# CAMAC_v2.net
KiCad netlist of a schematic drawn in Altium Designer
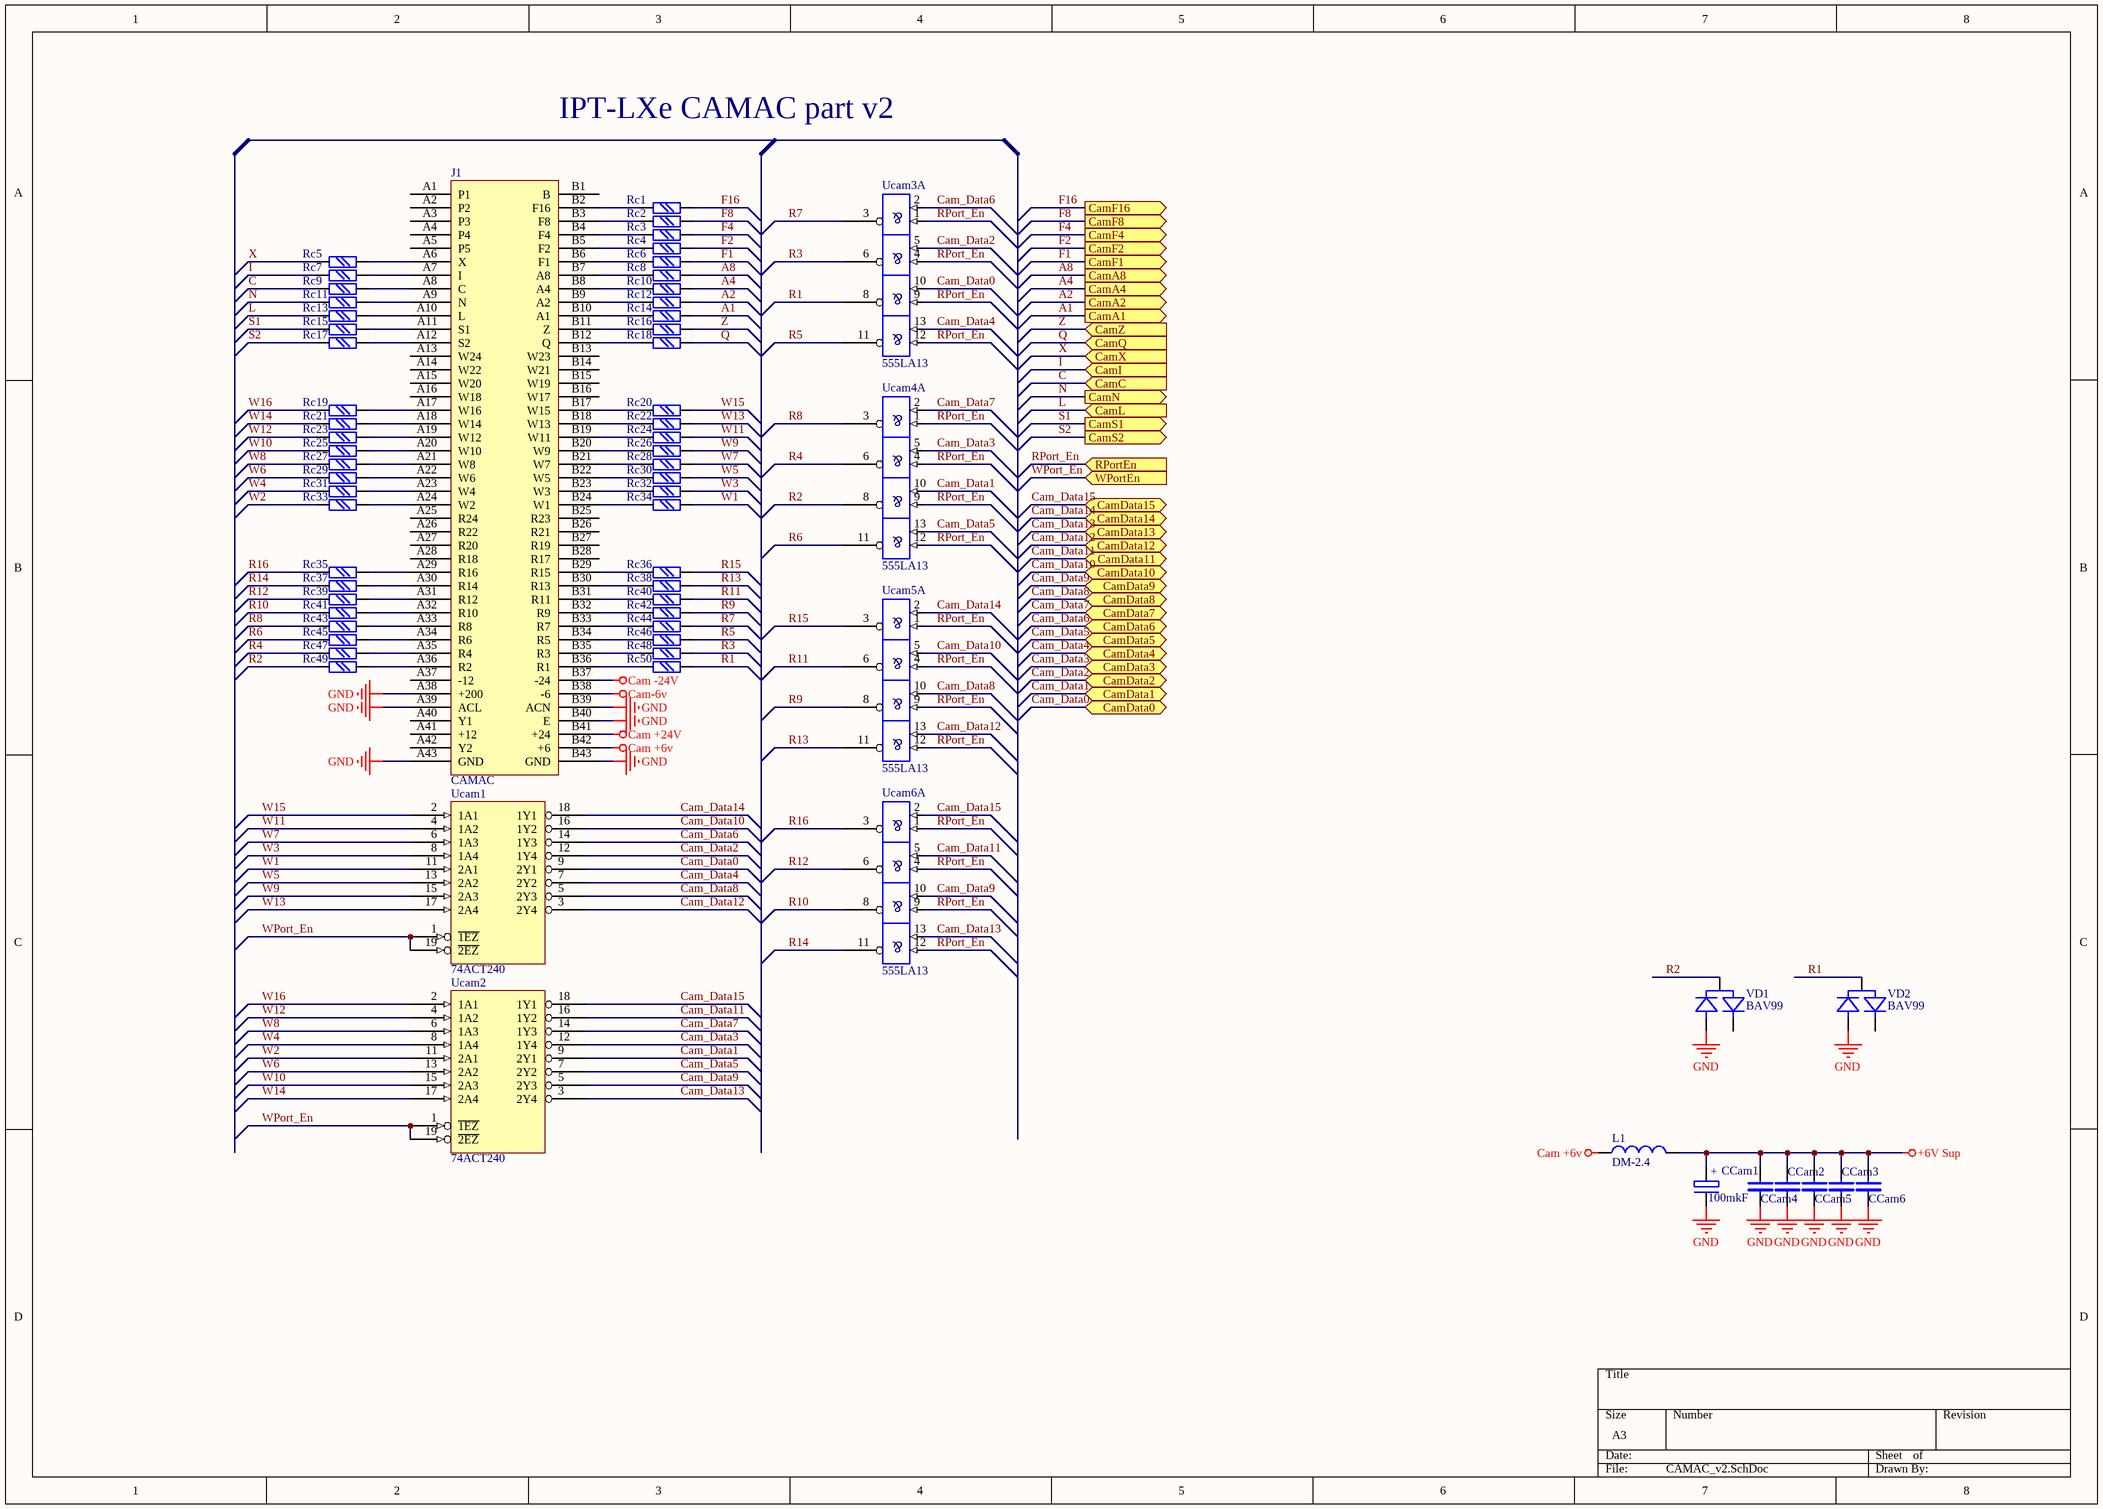
[diagram p0: CAMAC_v2.SchDoc]

(export (version "E")
  (design (tool "Eeschema 10.0.6"))
  (components
    (comp (ref "CCam1") (value "100mkF") (footprint "CEL-SMD300") (libsource (lib "vDevice") (part "C POL")))
    (comp (ref "CCam2") (value "0.1uF") (footprint "chip0805") (libsource (lib "vDevice") (part "C")))
    (comp (ref "CCam3") (value "0.1uF") (footprint "chip0805") (libsource (lib "vDevice") (part "C")))
    (comp (ref "CCam4") (value "0.1uF") (footprint "chip0805") (libsource (lib "vDevice") (part "C")))
    (comp (ref "CCam5") (value "0.1uF") (footprint "chip0805") (libsource (lib "vDevice") (part "C")))
    (comp (ref "CCam6") (value "0.1uF") (footprint "chip0805") (libsource (lib "vDevice") (part "C")))
    (comp (ref "J1") (value "CAMAC") (footprint "CAMAC - duplicate") (libsource (lib "*") (part "CAMACF")))
    (comp (ref "L1") (value "DM-2.4") (footprint "DM-2.4") (libsource (lib "*") (part "INDUCTOR")))
    (comp (ref "Rc1") (value "R") (footprint "chip0805") (libsource (lib "vDevice") (part "R")))
    (comp (ref "Rc2") (value "R") (footprint "chip0805") (libsource (lib "vDevice") (part "R")))
    (comp (ref "Rc3") (value "R") (footprint "chip0805") (libsource (lib "vDevice") (part "R")))
    (comp (ref "Rc4") (value "R") (footprint "chip0805") (libsource (lib "vDevice") (part "R")))
    (comp (ref "Rc5") (value "R") (footprint "chip0805") (libsource (lib "vDevice") (part "R")))
    (comp (ref "Rc6") (value "R") (footprint "chip0805") (libsource (lib "vDevice") (part "R")))
    (comp (ref "Rc7") (value "R") (footprint "chip0805") (libsource (lib "vDevice") (part "R")))
    (comp (ref "Rc8") (value "R") (footprint "chip0805") (libsource (lib "vDevice") (part "R")))
    (comp (ref "Rc9") (value "R") (footprint "chip0805") (libsource (lib "vDevice") (part "R")))
    (comp (ref "Rc10") (value "R") (footprint "chip0805") (libsource (lib "vDevice") (part "R")))
    (comp (ref "Rc11") (value "R") (footprint "chip0805") (libsource (lib "vDevice") (part "R")))
    (comp (ref "Rc12") (value "R") (footprint "chip0805") (libsource (lib "vDevice") (part "R")))
    (comp (ref "Rc13") (value "R") (footprint "chip0805") (libsource (lib "vDevice") (part "R")))
    (comp (ref "Rc14") (value "R") (footprint "chip0805") (libsource (lib "vDevice") (part "R")))
    (comp (ref "Rc15") (value "R") (footprint "chip0805") (libsource (lib "vDevice") (part "R")))
    (comp (ref "Rc16") (value "R") (footprint "chip0805") (libsource (lib "vDevice") (part "R")))
    (comp (ref "Rc17") (value "R") (footprint "chip0805") (libsource (lib "vDevice") (part "R")))
    (comp (ref "Rc18") (value "R") (footprint "chip0805") (libsource (lib "vDevice") (part "R")))
    (comp (ref "Rc19") (value "R") (footprint "chip0805") (libsource (lib "vDevice") (part "R")))
    (comp (ref "Rc20") (value "R") (footprint "chip0805") (libsource (lib "vDevice") (part "R")))
    (comp (ref "Rc21") (value "R") (footprint "chip0805") (libsource (lib "vDevice") (part "R")))
    (comp (ref "Rc22") (value "R") (footprint "chip0805") (libsource (lib "vDevice") (part "R")))
    (comp (ref "Rc23") (value "R") (footprint "chip0805") (libsource (lib "vDevice") (part "R")))
    (comp (ref "Rc24") (value "R") (footprint "chip0805") (libsource (lib "vDevice") (part "R")))
    (comp (ref "Rc25") (value "R") (footprint "chip0805") (libsource (lib "vDevice") (part "R")))
    (comp (ref "Rc26") (value "R") (footprint "chip0805") (libsource (lib "vDevice") (part "R")))
    (comp (ref "Rc27") (value "R") (footprint "chip0805") (libsource (lib "vDevice") (part "R")))
    (comp (ref "Rc28") (value "R") (footprint "chip0805") (libsource (lib "vDevice") (part "R")))
    (comp (ref "Rc29") (value "R") (footprint "chip0805") (libsource (lib "vDevice") (part "R")))
    (comp (ref "Rc30") (value "R") (footprint "chip0805") (libsource (lib "vDevice") (part "R")))
    (comp (ref "Rc31") (value "R") (footprint "chip0805") (libsource (lib "vDevice") (part "R")))
    (comp (ref "Rc32") (value "R") (footprint "chip0805") (libsource (lib "vDevice") (part "R")))
    (comp (ref "Rc33") (value "R") (footprint "chip0805") (libsource (lib "vDevice") (part "R")))
    (comp (ref "Rc34") (value "R") (footprint "chip0805") (libsource (lib "vDevice") (part "R")))
    (comp (ref "Rc35") (value "R") (footprint "chip0805") (libsource (lib "vDevice") (part "R")))
    (comp (ref "Rc36") (value "R") (footprint "chip0805") (libsource (lib "vDevice") (part "R")))
    (comp (ref "Rc37") (value "R") (footprint "chip0805") (libsource (lib "vDevice") (part "R")))
    (comp (ref "Rc38") (value "R") (footprint "chip0805") (libsource (lib "vDevice") (part "R")))
    (comp (ref "Rc39") (value "R") (footprint "chip0805") (libsource (lib "vDevice") (part "R")))
    (comp (ref "Rc40") (value "R") (footprint "chip0805") (libsource (lib "vDevice") (part "R")))
    (comp (ref "Rc41") (value "R") (footprint "chip0805") (libsource (lib "vDevice") (part "R")))
    (comp (ref "Rc42") (value "R") (footprint "chip0805") (libsource (lib "vDevice") (part "R")))
    (comp (ref "Rc43") (value "R") (footprint "chip0805") (libsource (lib "vDevice") (part "R")))
    (comp (ref "Rc44") (value "R") (footprint "chip0805") (libsource (lib "vDevice") (part "R")))
    (comp (ref "Rc45") (value "R") (footprint "chip0805") (libsource (lib "vDevice") (part "R")))
    (comp (ref "Rc46") (value "R") (footprint "chip0805") (libsource (lib "vDevice") (part "R")))
    (comp (ref "Rc47") (value "R") (footprint "chip0805") (libsource (lib "vDevice") (part "R")))
    (comp (ref "Rc48") (value "R") (footprint "chip0805") (libsource (lib "vDevice") (part "R")))
    (comp (ref "Rc49") (value "R") (footprint "chip0805") (libsource (lib "vDevice") (part "R")))
    (comp (ref "Rc50") (value "R") (footprint "chip0805") (libsource (lib "vDevice") (part "R")))
    (comp (ref "Ucam1") (value "74ACT240") (footprint "20SOIC300") (libsource (lib "*") (part "155AP3")))
    (comp (ref "Ucam2") (value "74ACT240") (footprint "20SOIC300") (libsource (lib "*") (part "155AP3")))
    (comp (ref "Ucam3") (value "555LA13") (footprint "14DIP300") (libsource (lib "vTTL") (part "555LA13")))
    (comp (ref "Ucam4") (value "555LA13") (footprint "14DIP300") (libsource (lib "vTTL") (part "555LA13")))
    (comp (ref "Ucam5") (value "555LA13") (footprint "14DIP300") (libsource (lib "vTTL") (part "555LA13")))
    (comp (ref "Ucam6") (value "555LA13") (footprint "14DIP300") (libsource (lib "vTTL") (part "555LA13")))
    (comp (ref "VD1")
      (value "BAV99")
      (footprint "SOT23")
      (description "Double diode")
      (libsource (lib "*") (part "BAV99"))
    )
    (comp (ref "VD2")
      (value "BAV99")
      (footprint "SOT23")
      (description "Double diode")
      (libsource (lib "*") (part "BAV99"))
    )
  )
  (nets
    (net (code "1") (name "+6V Sup") (class "Default")
      (node (ref "CCam1") (pin "+") (pinfunction "+_+") (pintype "passive"))
      (node (ref "CCam2") (pin "1") (pinfunction "1_1") (pintype "passive"))
      (node (ref "CCam3") (pin "1") (pinfunction "1_1") (pintype "passive"))
      (node (ref "CCam4") (pin "1") (pinfunction "1_1") (pintype "passive"))
      (node (ref "CCam5") (pin "1") (pinfunction "1_1") (pintype "passive"))
      (node (ref "CCam6") (pin "1") (pinfunction "1_1") (pintype "passive"))
      (node (ref "L1") (pin "2") (pinfunction "2_2") (pintype "passive"))
    )
    (net (code "2") (name "/A1") (class "Default")
      (node (ref "Rc14") (pin "2") (pinfunction "2_2") (pintype "passive"))
    )
    (net (code "3") (name "/A2") (class "Default")
      (node (ref "Rc12") (pin "2") (pinfunction "2_2") (pintype "passive"))
    )
    (net (code "4") (name "/A4") (class "Default")
      (node (ref "Rc10") (pin "2") (pinfunction "2_2") (pintype "passive"))
    )
    (net (code "5") (name "/A8") (class "Default")
      (node (ref "Rc8") (pin "2") (pinfunction "2_2") (pintype "passive"))
    )
    (net (code "6") (name "/C") (class "Default")
      (node (ref "Rc9") (pin "1") (pinfunction "1_1") (pintype "passive"))
    )
    (net (code "7") (name "/Cam_Data0") (class "Default")
      (node (ref "Ucam1") (pin "9") (pinfunction "2Y1_9") (pintype "tri_state"))
      (node (ref "Ucam3") (pin "10") (pinfunction "I1_10") (pintype "input"))
    )
    (net (code "8") (name "/Cam_Data1") (class "Default")
      (node (ref "Ucam2") (pin "9") (pinfunction "2Y1_9") (pintype "tri_state"))
      (node (ref "Ucam4") (pin "10") (pinfunction "I1_10") (pintype "input"))
    )
    (net (code "9") (name "/Cam_Data2") (class "Default")
      (node (ref "Ucam1") (pin "12") (pinfunction "1Y4_12") (pintype "tri_state"))
      (node (ref "Ucam3") (pin "5") (pinfunction "I1_5") (pintype "input"))
    )
    (net (code "10") (name "/Cam_Data3") (class "Default")
      (node (ref "Ucam2") (pin "12") (pinfunction "1Y4_12") (pintype "tri_state"))
      (node (ref "Ucam4") (pin "5") (pinfunction "I1_5") (pintype "input"))
    )
    (net (code "11") (name "/Cam_Data4") (class "Default")
      (node (ref "Ucam1") (pin "7") (pinfunction "2Y2_7") (pintype "tri_state"))
      (node (ref "Ucam3") (pin "13") (pinfunction "I1_13") (pintype "input"))
    )
    (net (code "12") (name "/Cam_Data5") (class "Default")
      (node (ref "Ucam2") (pin "7") (pinfunction "2Y2_7") (pintype "tri_state"))
      (node (ref "Ucam4") (pin "13") (pinfunction "I1_13") (pintype "input"))
    )
    (net (code "13") (name "/Cam_Data6") (class "Default")
      (node (ref "Ucam1") (pin "14") (pinfunction "1Y3_14") (pintype "tri_state"))
      (node (ref "Ucam3") (pin "2") (pinfunction "I1_2") (pintype "input"))
    )
    (net (code "14") (name "/Cam_Data7") (class "Default")
      (node (ref "Ucam2") (pin "14") (pinfunction "1Y3_14") (pintype "tri_state"))
      (node (ref "Ucam4") (pin "2") (pinfunction "I1_2") (pintype "input"))
    )
    (net (code "15") (name "/Cam_Data8") (class "Default")
      (node (ref "Ucam1") (pin "5") (pinfunction "2Y3_5") (pintype "tri_state"))
      (node (ref "Ucam5") (pin "10") (pinfunction "I1_10") (pintype "input"))
    )
    (net (code "16") (name "/Cam_Data9") (class "Default")
      (node (ref "Ucam2") (pin "5") (pinfunction "2Y3_5") (pintype "tri_state"))
      (node (ref "Ucam6") (pin "10") (pinfunction "I1_10") (pintype "input"))
    )
    (net (code "17") (name "/Cam_Data10") (class "Default")
      (node (ref "Ucam1") (pin "16") (pinfunction "1Y2_16") (pintype "tri_state"))
      (node (ref "Ucam5") (pin "5") (pinfunction "I1_5") (pintype "input"))
    )
    (net (code "18") (name "/Cam_Data11") (class "Default")
      (node (ref "Ucam2") (pin "16") (pinfunction "1Y2_16") (pintype "tri_state"))
      (node (ref "Ucam6") (pin "5") (pinfunction "I1_5") (pintype "input"))
    )
    (net (code "19") (name "/Cam_Data12") (class "Default")
      (node (ref "Ucam1") (pin "3") (pinfunction "2Y4_3") (pintype "tri_state"))
      (node (ref "Ucam5") (pin "13") (pinfunction "I1_13") (pintype "input"))
    )
    (net (code "20") (name "/Cam_Data13") (class "Default")
      (node (ref "Ucam2") (pin "3") (pinfunction "2Y4_3") (pintype "tri_state"))
      (node (ref "Ucam6") (pin "13") (pinfunction "I1_13") (pintype "input"))
    )
    (net (code "21") (name "/Cam_Data14") (class "Default")
      (node (ref "Ucam1") (pin "18") (pinfunction "1Y1_18") (pintype "tri_state"))
      (node (ref "Ucam5") (pin "2") (pinfunction "I1_2") (pintype "input"))
    )
    (net (code "22") (name "/Cam_Data15") (class "Default")
      (node (ref "Ucam2") (pin "18") (pinfunction "1Y1_18") (pintype "tri_state"))
      (node (ref "Ucam6") (pin "2") (pinfunction "I1_2") (pintype "input"))
    )
    (net (code "23") (name "/F1") (class "Default")
      (node (ref "Rc6") (pin "2") (pinfunction "2_2") (pintype "passive"))
    )
    (net (code "24") (name "/F2") (class "Default")
      (node (ref "Rc4") (pin "2") (pinfunction "2_2") (pintype "passive"))
    )
    (net (code "25") (name "/F4") (class "Default")
      (node (ref "Rc3") (pin "2") (pinfunction "2_2") (pintype "passive"))
    )
    (net (code "26") (name "/F8") (class "Default")
      (node (ref "Rc2") (pin "2") (pinfunction "2_2") (pintype "passive"))
    )
    (net (code "27") (name "/F16") (class "Default")
      (node (ref "Rc1") (pin "2") (pinfunction "2_2") (pintype "passive"))
    )
    (net (code "28") (name "/I") (class "Default")
      (node (ref "Rc7") (pin "1") (pinfunction "1_1") (pintype "passive"))
    )
    (net (code "29") (name "/L") (class "Default")
      (node (ref "Rc13") (pin "1") (pinfunction "1_1") (pintype "passive"))
    )
    (net (code "30") (name "/N") (class "Default")
      (node (ref "Rc11") (pin "1") (pinfunction "1_1") (pintype "passive"))
    )
    (net (code "31") (name "/Q") (class "Default")
      (node (ref "Rc18") (pin "2") (pinfunction "2_2") (pintype "passive"))
    )
    (net (code "32") (name "/R1") (class "Default")
      (node (ref "Rc50") (pin "1") (pinfunction "1_1") (pintype "passive"))
      (node (ref "Ucam3") (pin "8") (pinfunction "~{O}_8") (pintype "open_collector"))
      (node (ref "VD2") (pin "3") (pinfunction "3_3") (pintype "passive"))
    )
    (net (code "33") (name "/R2") (class "Default")
      (node (ref "Rc49") (pin "1") (pinfunction "1_1") (pintype "passive"))
      (node (ref "Ucam4") (pin "8") (pinfunction "~{O}_8") (pintype "open_collector"))
      (node (ref "VD1") (pin "3") (pinfunction "3_3") (pintype "passive"))
    )
    (net (code "34") (name "/R3") (class "Default")
      (node (ref "Rc48") (pin "2") (pinfunction "2_2") (pintype "passive"))
      (node (ref "Ucam3") (pin "6") (pinfunction "~{O}_6") (pintype "open_collector"))
    )
    (net (code "35") (name "/R4") (class "Default")
      (node (ref "Rc47") (pin "1") (pinfunction "1_1") (pintype "passive"))
      (node (ref "Ucam4") (pin "6") (pinfunction "~{O}_6") (pintype "open_collector"))
    )
    (net (code "36") (name "/R5") (class "Default")
      (node (ref "Rc46") (pin "2") (pinfunction "2_2") (pintype "passive"))
      (node (ref "Ucam3") (pin "11") (pinfunction "~{O}_11") (pintype "open_collector"))
    )
    (net (code "37") (name "/R6") (class "Default")
      (node (ref "Rc45") (pin "1") (pinfunction "1_1") (pintype "passive"))
      (node (ref "Ucam4") (pin "11") (pinfunction "~{O}_11") (pintype "open_collector"))
    )
    (net (code "38") (name "/R7") (class "Default")
      (node (ref "Rc44") (pin "2") (pinfunction "2_2") (pintype "passive"))
      (node (ref "Ucam3") (pin "3") (pinfunction "~{O}_3") (pintype "open_collector"))
    )
    (net (code "39") (name "/R8") (class "Default")
      (node (ref "Rc43") (pin "1") (pinfunction "1_1") (pintype "passive"))
      (node (ref "Ucam4") (pin "3") (pinfunction "~{O}_3") (pintype "open_collector"))
    )
    (net (code "40") (name "/R9") (class "Default")
      (node (ref "Rc42") (pin "2") (pinfunction "2_2") (pintype "passive"))
      (node (ref "Ucam5") (pin "8") (pinfunction "~{O}_8") (pintype "open_collector"))
    )
    (net (code "41") (name "/R10") (class "Default")
      (node (ref "Rc41") (pin "1") (pinfunction "1_1") (pintype "passive"))
      (node (ref "Ucam6") (pin "8") (pinfunction "~{O}_8") (pintype "open_collector"))
    )
    (net (code "42") (name "/R11") (class "Default")
      (node (ref "Rc40") (pin "2") (pinfunction "2_2") (pintype "passive"))
      (node (ref "Ucam5") (pin "6") (pinfunction "~{O}_6") (pintype "open_collector"))
    )
    (net (code "43") (name "/R12") (class "Default")
      (node (ref "Rc39") (pin "1") (pinfunction "1_1") (pintype "passive"))
      (node (ref "Ucam6") (pin "6") (pinfunction "~{O}_6") (pintype "open_collector"))
    )
    (net (code "44") (name "/R13") (class "Default")
      (node (ref "Rc38") (pin "2") (pinfunction "2_2") (pintype "passive"))
      (node (ref "Ucam5") (pin "11") (pinfunction "~{O}_11") (pintype "open_collector"))
    )
    (net (code "45") (name "/R14") (class "Default")
      (node (ref "Rc37") (pin "1") (pinfunction "1_1") (pintype "passive"))
      (node (ref "Ucam6") (pin "11") (pinfunction "~{O}_11") (pintype "open_collector"))
    )
    (net (code "46") (name "/R15") (class "Default")
      (node (ref "Rc36") (pin "2") (pinfunction "2_2") (pintype "passive"))
      (node (ref "Ucam5") (pin "3") (pinfunction "~{O}_3") (pintype "open_collector"))
    )
    (net (code "47") (name "/R16") (class "Default")
      (node (ref "Rc35") (pin "1") (pinfunction "1_1") (pintype "passive"))
      (node (ref "Ucam6") (pin "3") (pinfunction "~{O}_3") (pintype "open_collector"))
    )
    (net (code "48") (name "/RPort_En") (class "Default")
      (node (ref "Ucam3") (pin "1") (pinfunction "I0_1") (pintype "input"))
      (node (ref "Ucam3") (pin "12") (pinfunction "I0_12") (pintype "input"))
      (node (ref "Ucam3") (pin "4") (pinfunction "I0_4") (pintype "input"))
      (node (ref "Ucam3") (pin "9") (pinfunction "I0_9") (pintype "input"))
      (node (ref "Ucam4") (pin "1") (pinfunction "I0_1") (pintype "input"))
      (node (ref "Ucam4") (pin "12") (pinfunction "I0_12") (pintype "input"))
      (node (ref "Ucam4") (pin "4") (pinfunction "I0_4") (pintype "input"))
      (node (ref "Ucam4") (pin "9") (pinfunction "I0_9") (pintype "input"))
      (node (ref "Ucam5") (pin "1") (pinfunction "I0_1") (pintype "input"))
      (node (ref "Ucam5") (pin "12") (pinfunction "I0_12") (pintype "input"))
      (node (ref "Ucam5") (pin "4") (pinfunction "I0_4") (pintype "input"))
      (node (ref "Ucam5") (pin "9") (pinfunction "I0_9") (pintype "input"))
      (node (ref "Ucam6") (pin "1") (pinfunction "I0_1") (pintype "input"))
      (node (ref "Ucam6") (pin "12") (pinfunction "I0_12") (pintype "input"))
      (node (ref "Ucam6") (pin "4") (pinfunction "I0_4") (pintype "input"))
      (node (ref "Ucam6") (pin "9") (pinfunction "I0_9") (pintype "input"))
    )
    (net (code "49") (name "/S1") (class "Default")
      (node (ref "Rc15") (pin "1") (pinfunction "1_1") (pintype "passive"))
    )
    (net (code "50") (name "/S2") (class "Default")
      (node (ref "Rc17") (pin "1") (pinfunction "1_1") (pintype "passive"))
    )
    (net (code "51") (name "/W1") (class "Default")
      (node (ref "Rc34") (pin "2") (pinfunction "2_2") (pintype "passive"))
      (node (ref "Ucam1") (pin "11") (pinfunction "2A1_11") (pintype "input"))
    )
    (net (code "52") (name "/W2") (class "Default")
      (node (ref "Rc33") (pin "1") (pinfunction "1_1") (pintype "passive"))
      (node (ref "Ucam2") (pin "11") (pinfunction "2A1_11") (pintype "input"))
    )
    (net (code "53") (name "/W3") (class "Default")
      (node (ref "Rc32") (pin "2") (pinfunction "2_2") (pintype "passive"))
      (node (ref "Ucam1") (pin "8") (pinfunction "1A4_8") (pintype "input"))
    )
    (net (code "54") (name "/W4") (class "Default")
      (node (ref "Rc31") (pin "1") (pinfunction "1_1") (pintype "passive"))
      (node (ref "Ucam2") (pin "8") (pinfunction "1A4_8") (pintype "input"))
    )
    (net (code "55") (name "/W5") (class "Default")
      (node (ref "Rc30") (pin "2") (pinfunction "2_2") (pintype "passive"))
      (node (ref "Ucam1") (pin "13") (pinfunction "2A2_13") (pintype "input"))
    )
    (net (code "56") (name "/W6") (class "Default")
      (node (ref "Rc29") (pin "1") (pinfunction "1_1") (pintype "passive"))
      (node (ref "Ucam2") (pin "13") (pinfunction "2A2_13") (pintype "input"))
    )
    (net (code "57") (name "/W7") (class "Default")
      (node (ref "Rc28") (pin "2") (pinfunction "2_2") (pintype "passive"))
      (node (ref "Ucam1") (pin "6") (pinfunction "1A3_6") (pintype "input"))
    )
    (net (code "58") (name "/W8") (class "Default")
      (node (ref "Rc27") (pin "1") (pinfunction "1_1") (pintype "passive"))
      (node (ref "Ucam2") (pin "6") (pinfunction "1A3_6") (pintype "input"))
    )
    (net (code "59") (name "/W9") (class "Default")
      (node (ref "Rc26") (pin "2") (pinfunction "2_2") (pintype "passive"))
      (node (ref "Ucam1") (pin "15") (pinfunction "2A3_15") (pintype "input"))
    )
    (net (code "60") (name "/W10") (class "Default")
      (node (ref "Rc25") (pin "1") (pinfunction "1_1") (pintype "passive"))
      (node (ref "Ucam2") (pin "15") (pinfunction "2A3_15") (pintype "input"))
    )
    (net (code "61") (name "/W11") (class "Default")
      (node (ref "Rc24") (pin "2") (pinfunction "2_2") (pintype "passive"))
      (node (ref "Ucam1") (pin "4") (pinfunction "1A2_4") (pintype "input"))
    )
    (net (code "62") (name "/W12") (class "Default")
      (node (ref "Rc23") (pin "1") (pinfunction "1_1") (pintype "passive"))
      (node (ref "Ucam2") (pin "4") (pinfunction "1A2_4") (pintype "input"))
    )
    (net (code "63") (name "/W13") (class "Default")
      (node (ref "Rc22") (pin "2") (pinfunction "2_2") (pintype "passive"))
      (node (ref "Ucam1") (pin "17") (pinfunction "2A4_17") (pintype "input"))
    )
    (net (code "64") (name "/W14") (class "Default")
      (node (ref "Rc21") (pin "1") (pinfunction "1_1") (pintype "passive"))
      (node (ref "Ucam2") (pin "17") (pinfunction "2A4_17") (pintype "input"))
    )
    (net (code "65") (name "/W15") (class "Default")
      (node (ref "Rc20") (pin "2") (pinfunction "2_2") (pintype "passive"))
      (node (ref "Ucam1") (pin "2") (pinfunction "1A1_2") (pintype "input"))
    )
    (net (code "66") (name "/W16") (class "Default")
      (node (ref "Rc19") (pin "1") (pinfunction "1_1") (pintype "passive"))
      (node (ref "Ucam2") (pin "2") (pinfunction "1A1_2") (pintype "input"))
    )
    (net (code "67") (name "/WPort_En") (class "Default")
      (node (ref "Ucam1") (pin "1") (pinfunction "~{1EZ}_1") (pintype "input"))
      (node (ref "Ucam1") (pin "19") (pinfunction "~{2EZ}_19") (pintype "input"))
      (node (ref "Ucam2") (pin "1") (pinfunction "~{1EZ}_1") (pintype "input"))
      (node (ref "Ucam2") (pin "19") (pinfunction "~{2EZ}_19") (pintype "input"))
    )
    (net (code "68") (name "/X") (class "Default")
      (node (ref "Rc5") (pin "1") (pinfunction "1_1") (pintype "passive"))
    )
    (net (code "69") (name "/Z") (class "Default")
      (node (ref "Rc16") (pin "2") (pinfunction "2_2") (pintype "passive"))
    )
    (net (code "70") (name "Cam +6v") (class "Default")
      (node (ref "J1") (pin "B42") (pinfunction "+6_B42") (pintype "passive"))
      (node (ref "L1") (pin "1") (pinfunction "1_1") (pintype "passive"))
    )
    (net (code "71") (name "Cam +24V") (class "Default")
      (node (ref "J1") (pin "B41") (pinfunction "+24_B41") (pintype "passive"))
    )
    (net (code "72") (name "Cam -24V") (class "Default")
      (node (ref "J1") (pin "B37") (pinfunction "-24_B37") (pintype "passive"))
    )
    (net (code "73") (name "Cam-6v") (class "Default")
      (node (ref "J1") (pin "B38") (pinfunction "-6_B38") (pintype "passive"))
    )
    (net (code "74") (name "GND") (class "Default")
      (node (ref "CCam1") (pin "-") (pinfunction "-_-") (pintype "passive"))
      (node (ref "CCam2") (pin "2") (pinfunction "2_2") (pintype "passive"))
      (node (ref "CCam3") (pin "2") (pinfunction "2_2") (pintype "passive"))
      (node (ref "CCam4") (pin "2") (pinfunction "2_2") (pintype "passive"))
      (node (ref "CCam5") (pin "2") (pinfunction "2_2") (pintype "passive"))
      (node (ref "CCam6") (pin "2") (pinfunction "2_2") (pintype "passive"))
      (node (ref "J1") (pin "A38") (pinfunction "+200_A38") (pintype "passive"))
      (node (ref "J1") (pin "A39") (pinfunction "ACL_A39") (pintype "passive"))
      (node (ref "J1") (pin "A43") (pinfunction "GND_A43") (pintype "passive"))
      (node (ref "J1") (pin "B39") (pinfunction "ACN_B39") (pintype "passive"))
      (node (ref "J1") (pin "B40") (pinfunction "E_B40") (pintype "passive"))
      (node (ref "J1") (pin "B43") (pinfunction "GND_B43") (pintype "passive"))
      (node (ref "Ucam1") (pin "10") (pinfunction "GND_10") (pintype "power_in"))
      (node (ref "Ucam2") (pin "10") (pinfunction "GND_10") (pintype "power_in"))
      (node (ref "VD1") (pin "1") (pinfunction "1_1") (pintype "passive"))
      (node (ref "VD2") (pin "1") (pinfunction "1_1") (pintype "passive"))
    )
    (net (code "75") (name "Net-(J1-A1)") (class "Default")
      (node (ref "J1") (pin "B10") (pinfunction "A1_B10") (pintype "passive"))
      (node (ref "Rc14") (pin "1") (pinfunction "1_1") (pintype "passive"))
    )
    (net (code "76") (name "Net-(J1-A2)") (class "Default")
      (node (ref "J1") (pin "B9") (pinfunction "A2_B9") (pintype "passive"))
      (node (ref "Rc12") (pin "1") (pinfunction "1_1") (pintype "passive"))
    )
    (net (code "77") (name "Net-(J1-A4)") (class "Default")
      (node (ref "J1") (pin "B8") (pinfunction "A4_B8") (pintype "passive"))
      (node (ref "Rc10") (pin "1") (pinfunction "1_1") (pintype "passive"))
    )
    (net (code "78") (name "Net-(J1-A8)") (class "Default")
      (node (ref "J1") (pin "B7") (pinfunction "A8_B7") (pintype "passive"))
      (node (ref "Rc8") (pin "1") (pinfunction "1_1") (pintype "passive"))
    )
    (net (code "79") (name "Net-(J1-C)") (class "Default")
      (node (ref "J1") (pin "A8") (pinfunction "C_A8") (pintype "passive"))
      (node (ref "Rc9") (pin "2") (pinfunction "2_2") (pintype "passive"))
    )
    (net (code "80") (name "Net-(J1-F1)") (class "Default")
      (node (ref "J1") (pin "B6") (pinfunction "F1_B6") (pintype "passive"))
      (node (ref "Rc6") (pin "1") (pinfunction "1_1") (pintype "passive"))
    )
    (net (code "81") (name "Net-(J1-F2)") (class "Default")
      (node (ref "J1") (pin "B5") (pinfunction "F2_B5") (pintype "passive"))
      (node (ref "Rc4") (pin "1") (pinfunction "1_1") (pintype "passive"))
    )
    (net (code "82") (name "Net-(J1-F4)") (class "Default")
      (node (ref "J1") (pin "B4") (pinfunction "F4_B4") (pintype "passive"))
      (node (ref "Rc3") (pin "1") (pinfunction "1_1") (pintype "passive"))
    )
    (net (code "83") (name "Net-(J1-F8)") (class "Default")
      (node (ref "J1") (pin "B3") (pinfunction "F8_B3") (pintype "passive"))
      (node (ref "Rc2") (pin "1") (pinfunction "1_1") (pintype "passive"))
    )
    (net (code "84") (name "Net-(J1-F16)") (class "Default")
      (node (ref "J1") (pin "B2") (pinfunction "F16_B2") (pintype "passive"))
      (node (ref "Rc1") (pin "1") (pinfunction "1_1") (pintype "passive"))
    )
    (net (code "85") (name "Net-(J1-I)") (class "Default")
      (node (ref "J1") (pin "A7") (pinfunction "I_A7") (pintype "passive"))
      (node (ref "Rc7") (pin "2") (pinfunction "2_2") (pintype "passive"))
    )
    (net (code "86") (name "Net-(J1-L)") (class "Default")
      (node (ref "J1") (pin "A10") (pinfunction "L_A10") (pintype "passive"))
      (node (ref "Rc13") (pin "2") (pinfunction "2_2") (pintype "passive"))
    )
    (net (code "87") (name "Net-(J1-N)") (class "Default")
      (node (ref "J1") (pin "A9") (pinfunction "N_A9") (pintype "passive"))
      (node (ref "Rc11") (pin "2") (pinfunction "2_2") (pintype "passive"))
    )
    (net (code "88") (name "Net-(J1-Q)") (class "Default")
      (node (ref "J1") (pin "B12") (pinfunction "Q_B12") (pintype "passive"))
      (node (ref "Rc18") (pin "1") (pinfunction "1_1") (pintype "passive"))
    )
    (net (code "89") (name "Net-(J1-R1)") (class "Default")
      (node (ref "J1") (pin "B36") (pinfunction "R1_B36") (pintype "passive"))
      (node (ref "Rc50") (pin "2") (pinfunction "2_2") (pintype "passive"))
    )
    (net (code "90") (name "Net-(J1-R2)") (class "Default")
      (node (ref "J1") (pin "A36") (pinfunction "R2_A36") (pintype "passive"))
      (node (ref "Rc49") (pin "2") (pinfunction "2_2") (pintype "passive"))
    )
    (net (code "91") (name "Net-(J1-R3)") (class "Default")
      (node (ref "J1") (pin "B35") (pinfunction "R3_B35") (pintype "passive"))
      (node (ref "Rc48") (pin "1") (pinfunction "1_1") (pintype "passive"))
    )
    (net (code "92") (name "Net-(J1-R4)") (class "Default")
      (node (ref "J1") (pin "A35") (pinfunction "R4_A35") (pintype "passive"))
      (node (ref "Rc47") (pin "2") (pinfunction "2_2") (pintype "passive"))
    )
    (net (code "93") (name "Net-(J1-R5)") (class "Default")
      (node (ref "J1") (pin "B34") (pinfunction "R5_B34") (pintype "passive"))
      (node (ref "Rc46") (pin "1") (pinfunction "1_1") (pintype "passive"))
    )
    (net (code "94") (name "Net-(J1-R6)") (class "Default")
      (node (ref "J1") (pin "A34") (pinfunction "R6_A34") (pintype "passive"))
      (node (ref "Rc45") (pin "2") (pinfunction "2_2") (pintype "passive"))
    )
    (net (code "95") (name "Net-(J1-R7)") (class "Default")
      (node (ref "J1") (pin "B33") (pinfunction "R7_B33") (pintype "passive"))
      (node (ref "Rc44") (pin "1") (pinfunction "1_1") (pintype "passive"))
    )
    (net (code "96") (name "Net-(J1-R8)") (class "Default")
      (node (ref "J1") (pin "A33") (pinfunction "R8_A33") (pintype "passive"))
      (node (ref "Rc43") (pin "2") (pinfunction "2_2") (pintype "passive"))
    )
    (net (code "97") (name "Net-(J1-R9)") (class "Default")
      (node (ref "J1") (pin "B32") (pinfunction "R9_B32") (pintype "passive"))
      (node (ref "Rc42") (pin "1") (pinfunction "1_1") (pintype "passive"))
    )
    (net (code "98") (name "Net-(J1-R10)") (class "Default")
      (node (ref "J1") (pin "A32") (pinfunction "R10_A32") (pintype "passive"))
      (node (ref "Rc41") (pin "2") (pinfunction "2_2") (pintype "passive"))
    )
    (net (code "99") (name "Net-(J1-R11)") (class "Default")
      (node (ref "J1") (pin "B31") (pinfunction "R11_B31") (pintype "passive"))
      (node (ref "Rc40") (pin "1") (pinfunction "1_1") (pintype "passive"))
    )
    (net (code "100") (name "Net-(J1-R12)") (class "Default")
      (node (ref "J1") (pin "A31") (pinfunction "R12_A31") (pintype "passive"))
      (node (ref "Rc39") (pin "2") (pinfunction "2_2") (pintype "passive"))
    )
    (net (code "101") (name "Net-(J1-R13)") (class "Default")
      (node (ref "J1") (pin "B30") (pinfunction "R13_B30") (pintype "passive"))
      (node (ref "Rc38") (pin "1") (pinfunction "1_1") (pintype "passive"))
    )
    (net (code "102") (name "Net-(J1-R14)") (class "Default")
      (node (ref "J1") (pin "A30") (pinfunction "R14_A30") (pintype "passive"))
      (node (ref "Rc37") (pin "2") (pinfunction "2_2") (pintype "passive"))
    )
    (net (code "103") (name "Net-(J1-R15)") (class "Default")
      (node (ref "J1") (pin "B29") (pinfunction "R15_B29") (pintype "passive"))
      (node (ref "Rc36") (pin "1") (pinfunction "1_1") (pintype "passive"))
    )
    (net (code "104") (name "Net-(J1-R16)") (class "Default")
      (node (ref "J1") (pin "A29") (pinfunction "R16_A29") (pintype "passive"))
      (node (ref "Rc35") (pin "2") (pinfunction "2_2") (pintype "passive"))
    )
    (net (code "105") (name "Net-(J1-S1)") (class "Default")
      (node (ref "J1") (pin "A11") (pinfunction "S1_A11") (pintype "passive"))
      (node (ref "Rc15") (pin "2") (pinfunction "2_2") (pintype "passive"))
    )
    (net (code "106") (name "Net-(J1-S2)") (class "Default")
      (node (ref "J1") (pin "A12") (pinfunction "S2_A12") (pintype "passive"))
      (node (ref "Rc17") (pin "2") (pinfunction "2_2") (pintype "passive"))
    )
    (net (code "107") (name "Net-(J1-W1)") (class "Default")
      (node (ref "J1") (pin "B24") (pinfunction "W1_B24") (pintype "passive"))
      (node (ref "Rc34") (pin "1") (pinfunction "1_1") (pintype "passive"))
    )
    (net (code "108") (name "Net-(J1-W2)") (class "Default")
      (node (ref "J1") (pin "A24") (pinfunction "W2_A24") (pintype "passive"))
      (node (ref "Rc33") (pin "2") (pinfunction "2_2") (pintype "passive"))
    )
    (net (code "109") (name "Net-(J1-W3)") (class "Default")
      (node (ref "J1") (pin "B23") (pinfunction "W3_B23") (pintype "passive"))
      (node (ref "Rc32") (pin "1") (pinfunction "1_1") (pintype "passive"))
    )
    (net (code "110") (name "Net-(J1-W4)") (class "Default")
      (node (ref "J1") (pin "A23") (pinfunction "W4_A23") (pintype "passive"))
      (node (ref "Rc31") (pin "2") (pinfunction "2_2") (pintype "passive"))
    )
    (net (code "111") (name "Net-(J1-W5)") (class "Default")
      (node (ref "J1") (pin "B22") (pinfunction "W5_B22") (pintype "passive"))
      (node (ref "Rc30") (pin "1") (pinfunction "1_1") (pintype "passive"))
    )
    (net (code "112") (name "Net-(J1-W6)") (class "Default")
      (node (ref "J1") (pin "A22") (pinfunction "W6_A22") (pintype "passive"))
      (node (ref "Rc29") (pin "2") (pinfunction "2_2") (pintype "passive"))
    )
    (net (code "113") (name "Net-(J1-W7)") (class "Default")
      (node (ref "J1") (pin "B21") (pinfunction "W7_B21") (pintype "passive"))
      (node (ref "Rc28") (pin "1") (pinfunction "1_1") (pintype "passive"))
    )
    (net (code "114") (name "Net-(J1-W8)") (class "Default")
      (node (ref "J1") (pin "A21") (pinfunction "W8_A21") (pintype "passive"))
      (node (ref "Rc27") (pin "2") (pinfunction "2_2") (pintype "passive"))
    )
    (net (code "115") (name "Net-(J1-W9)") (class "Default")
      (node (ref "J1") (pin "B20") (pinfunction "W9_B20") (pintype "passive"))
      (node (ref "Rc26") (pin "1") (pinfunction "1_1") (pintype "passive"))
    )
    (net (code "116") (name "Net-(J1-W10)") (class "Default")
      (node (ref "J1") (pin "A20") (pinfunction "W10_A20") (pintype "passive"))
      (node (ref "Rc25") (pin "2") (pinfunction "2_2") (pintype "passive"))
    )
    (net (code "117") (name "Net-(J1-W11)") (class "Default")
      (node (ref "J1") (pin "B19") (pinfunction "W11_B19") (pintype "passive"))
      (node (ref "Rc24") (pin "1") (pinfunction "1_1") (pintype "passive"))
    )
    (net (code "118") (name "Net-(J1-W12)") (class "Default")
      (node (ref "J1") (pin "A19") (pinfunction "W12_A19") (pintype "passive"))
      (node (ref "Rc23") (pin "2") (pinfunction "2_2") (pintype "passive"))
    )
    (net (code "119") (name "Net-(J1-W13)") (class "Default")
      (node (ref "J1") (pin "B18") (pinfunction "W13_B18") (pintype "passive"))
      (node (ref "Rc22") (pin "1") (pinfunction "1_1") (pintype "passive"))
    )
    (net (code "120") (name "Net-(J1-W14)") (class "Default")
      (node (ref "J1") (pin "A18") (pinfunction "W14_A18") (pintype "passive"))
      (node (ref "Rc21") (pin "2") (pinfunction "2_2") (pintype "passive"))
    )
    (net (code "121") (name "Net-(J1-W15)") (class "Default")
      (node (ref "J1") (pin "B17") (pinfunction "W15_B17") (pintype "passive"))
      (node (ref "Rc20") (pin "1") (pinfunction "1_1") (pintype "passive"))
    )
    (net (code "122") (name "Net-(J1-W16)") (class "Default")
      (node (ref "J1") (pin "A17") (pinfunction "W16_A17") (pintype "passive"))
      (node (ref "Rc19") (pin "2") (pinfunction "2_2") (pintype "passive"))
    )
    (net (code "123") (name "Net-(J1-X)") (class "Default")
      (node (ref "J1") (pin "A6") (pinfunction "X_A6") (pintype "passive"))
      (node (ref "Rc5") (pin "2") (pinfunction "2_2") (pintype "passive"))
    )
    (net (code "124") (name "Net-(J1-Z)") (class "Default")
      (node (ref "J1") (pin "B11") (pinfunction "Z_B11") (pintype "passive"))
      (node (ref "Rc16") (pin "1") (pinfunction "1_1") (pintype "passive"))
    )
    (net (code "125") (name "VCC") (class "Default")
      (node (ref "Ucam1") (pin "20") (pinfunction "VCC_20") (pintype "power_in"))
      (node (ref "Ucam2") (pin "20") (pinfunction "VCC_20") (pintype "power_in"))
    )
    (net (code "126") (name "unconnected-(J1-+12-PadA41)") (class "Default")
      (node (ref "J1") (pin "A41") (pinfunction "+12_A41") (pintype "passive"))
    )
    (net (code "127") (name "unconnected-(J1--12-PadA37)") (class "Default")
      (node (ref "J1") (pin "A37") (pinfunction "-12_A37") (pintype "passive"))
    )
    (net (code "128") (name "unconnected-(J1-B-PadB1)") (class "Default")
      (node (ref "J1") (pin "B1") (pinfunction "B_B1") (pintype "passive"))
    )
    (net (code "129") (name "unconnected-(J1-P1-PadA1)") (class "Default")
      (node (ref "J1") (pin "A1") (pinfunction "P1_A1") (pintype "passive"))
    )
    (net (code "130") (name "unconnected-(J1-P2-PadA2)") (class "Default")
      (node (ref "J1") (pin "A2") (pinfunction "P2_A2") (pintype "passive"))
    )
    (net (code "131") (name "unconnected-(J1-P3-PadA3)") (class "Default")
      (node (ref "J1") (pin "A3") (pinfunction "P3_A3") (pintype "passive"))
    )
    (net (code "132") (name "unconnected-(J1-P4-PadA4)") (class "Default")
      (node (ref "J1") (pin "A4") (pinfunction "P4_A4") (pintype "passive"))
    )
    (net (code "133") (name "unconnected-(J1-P5-PadA5)") (class "Default")
      (node (ref "J1") (pin "A5") (pinfunction "P5_A5") (pintype "passive"))
    )
    (net (code "134") (name "unconnected-(J1-R17-PadB28)") (class "Default")
      (node (ref "J1") (pin "B28") (pinfunction "R17_B28") (pintype "passive"))
    )
    (net (code "135") (name "unconnected-(J1-R18-PadA28)") (class "Default")
      (node (ref "J1") (pin "A28") (pinfunction "R18_A28") (pintype "passive"))
    )
    (net (code "136") (name "unconnected-(J1-R19-PadB27)") (class "Default")
      (node (ref "J1") (pin "B27") (pinfunction "R19_B27") (pintype "passive"))
    )
    (net (code "137") (name "unconnected-(J1-R20-PadA27)") (class "Default")
      (node (ref "J1") (pin "A27") (pinfunction "R20_A27") (pintype "passive"))
    )
    (net (code "138") (name "unconnected-(J1-R21-PadB26)") (class "Default")
      (node (ref "J1") (pin "B26") (pinfunction "R21_B26") (pintype "passive"))
    )
    (net (code "139") (name "unconnected-(J1-R22-PadA26)") (class "Default")
      (node (ref "J1") (pin "A26") (pinfunction "R22_A26") (pintype "passive"))
    )
    (net (code "140") (name "unconnected-(J1-R23-PadB25)") (class "Default")
      (node (ref "J1") (pin "B25") (pinfunction "R23_B25") (pintype "passive"))
    )
    (net (code "141") (name "unconnected-(J1-R24-PadA25)") (class "Default")
      (node (ref "J1") (pin "A25") (pinfunction "R24_A25") (pintype "passive"))
    )
    (net (code "142") (name "unconnected-(J1-W17-PadB16)") (class "Default")
      (node (ref "J1") (pin "B16") (pinfunction "W17_B16") (pintype "passive"))
    )
    (net (code "143") (name "unconnected-(J1-W18-PadA16)") (class "Default")
      (node (ref "J1") (pin "A16") (pinfunction "W18_A16") (pintype "passive"))
    )
    (net (code "144") (name "unconnected-(J1-W19-PadB15)") (class "Default")
      (node (ref "J1") (pin "B15") (pinfunction "W19_B15") (pintype "passive"))
    )
    (net (code "145") (name "unconnected-(J1-W20-PadA15)") (class "Default")
      (node (ref "J1") (pin "A15") (pinfunction "W20_A15") (pintype "passive"))
    )
    (net (code "146") (name "unconnected-(J1-W21-PadB14)") (class "Default")
      (node (ref "J1") (pin "B14") (pinfunction "W21_B14") (pintype "passive"))
    )
    (net (code "147") (name "unconnected-(J1-W22-PadA14)") (class "Default")
      (node (ref "J1") (pin "A14") (pinfunction "W22_A14") (pintype "passive"))
    )
    (net (code "148") (name "unconnected-(J1-W23-PadB13)") (class "Default")
      (node (ref "J1") (pin "B13") (pinfunction "W23_B13") (pintype "passive"))
    )
    (net (code "149") (name "unconnected-(J1-W24-PadA13)") (class "Default")
      (node (ref "J1") (pin "A13") (pinfunction "W24_A13") (pintype "passive"))
    )
    (net (code "150") (name "unconnected-(J1-Y1-PadA40)") (class "Default")
      (node (ref "J1") (pin "A40") (pinfunction "Y1_A40") (pintype "passive"))
    )
    (net (code "151") (name "unconnected-(J1-Y2-PadA42)") (class "Default")
      (node (ref "J1") (pin "A42") (pinfunction "Y2_A42") (pintype "passive"))
    )
    (net (code "152") (name "unconnected-(VD1-Pad2)") (class "Default")
      (node (ref "VD1") (pin "2") (pinfunction "2_2") (pintype "passive"))
    )
    (net (code "153") (name "unconnected-(VD2-Pad2)") (class "Default")
      (node (ref "VD2") (pin "2") (pinfunction "2_2") (pintype "passive"))
    )
  )
)
